# basic_attiny85.net
KiCad netlist of a schematic drawn in EAGLE
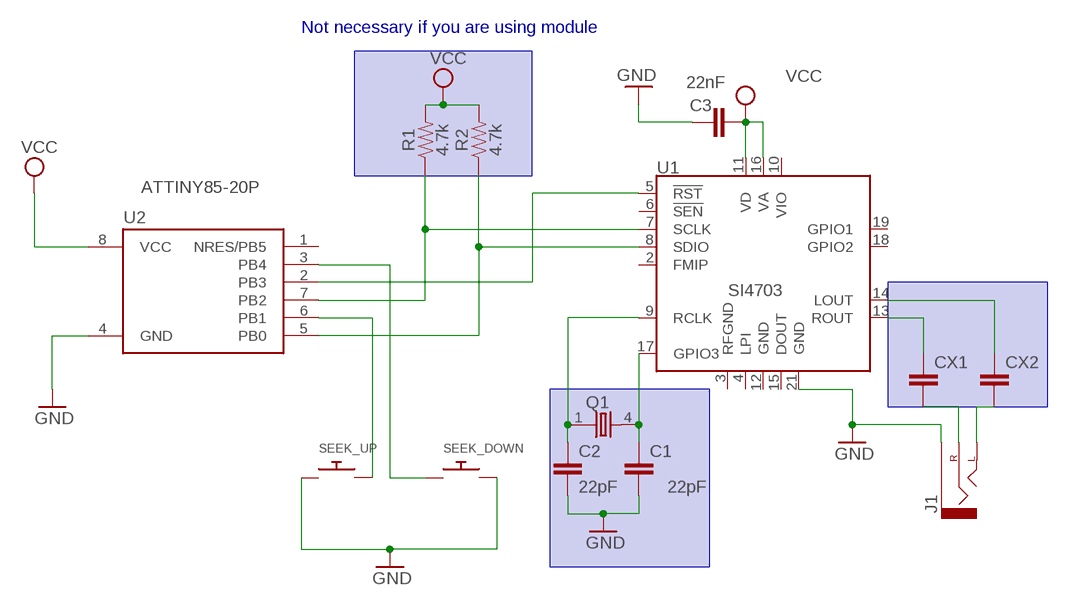
[diagram p0: schematic, sheet 1]

(export (version "E")
  (design (tool "Eeschema 10.0.6"))
  (components
    (comp (ref "C1")
      (value "22pF")
      (footprint "eagle-import:C2.5-3")
      (libsource (lib "eagle-import") (part "C2,5-3"))
    )
    (comp (ref "C2")
      (value "22pF")
      (footprint "eagle-import:C2.5-3")
      (libsource (lib "eagle-import") (part "C2,5-3"))
    )
    (comp (ref "C3")
      (value "22nF")
      (footprint "eagle-import:C2.5-3")
      (libsource (lib "eagle-import") (part "C2,5-3"))
    )
    (comp (ref "CX1")
      (value "CXXC10B6")
      (footprint "eagle-import:XC10B6")
      (libsource (lib "eagle-import") (part "CXXC10B6"))
    )
    (comp (ref "CX2")
      (value "CXXC10B6")
      (footprint "eagle-import:XC10B6")
      (libsource (lib "eagle-import") (part "CXXC10B6"))
    )
    (comp (ref "J1")
      (value "AUDIO_JACK_2.5MM_HOLESONLY")
      (footprint "eagle-import:STEREOJACK2.5MM_SPECIAL_HOLES-ONLY")
      (libsource (lib "eagle-import") (part "AUDIO_JACK_2.5MM_HOLESONLY"))
    )
    (comp (ref "Q1")
      (value "86SMX")
      (footprint "eagle-import:86SMX")
      (fields (field (name "MF") "C-MAC  FREQUENCY PRODUCTS LTD") (field (name "MPN") "XTAL003321- 86SMX"))
      (libsource (lib "eagle-import") (part "86SMX"))
    )
    (comp (ref "R1")
      (value "4.7k")
      (footprint "eagle-import:0603")
      (libsource (lib "eagle-import") (part "4.7KOHM-0603-1/10W-1%"))
    )
    (comp (ref "R2")
      (value "4.7k")
      (footprint "eagle-import:0603")
      (libsource (lib "eagle-import") (part "4.7KOHM-0603-1/10W-1%"))
    )
    (comp (ref "SEEK_DOWN")
      (value "SWITCH_PUSHBUTTONC&K_KSS")
      (footprint "eagle-import:BTN_CK_KSS")
      (libsource (lib "eagle-import") (part "SWITCH_PUSHBUTTONC&K_KSS"))
    )
    (comp (ref "SEEK_UP")
      (value "SWITCH_PUSHBUTTONC&K_KSS")
      (footprint "eagle-import:BTN_CK_KSS")
      (libsource (lib "eagle-import") (part "SWITCH_PUSHBUTTONC&K_KSS"))
    )
    (comp (ref "U1")
      (value "SI4703")
      (footprint "eagle-import:QFN-20-3X3MM")
      (fields (field (name "MF") "SparkFun Electronics"))
      (libsource (lib "eagle-import") (part "SI4703"))
    )
    (comp (ref "U2")
      (value "ATTINY85-20P")
      (footprint "eagle-import:PDIP08_300MIL")
      (libsource (lib "eagle-import") (part "ATTINY85P-20"))
    )
  )
  (nets
    (net (code "1") (name "GND") (class "Default")
      (node (ref "C1") (pin "2") (pinfunction "2_2") (pintype "passive"))
      (node (ref "C2") (pin "2") (pinfunction "2_2") (pintype "passive"))
      (node (ref "C3") (pin "1") (pinfunction "1_1") (pintype "passive"))
      (node (ref "J1") (pin "RING1") (pinfunction "SLEEVE_RING1") (pintype "bidirectional"))
      (node (ref "SEEK_DOWN") (pin "P$2") (pinfunction "P$2_P$2") (pintype "passive"))
      (node (ref "SEEK_UP") (pin "P$1") (pinfunction "P$1_P$1") (pintype "passive"))
      (node (ref "U1") (pin "21") (pinfunction "GND_21") (pintype "bidirectional"))
      (node (ref "U2") (pin "4") (pinfunction "GND_4") (pintype "power_in"))
    )
    (net (code "2") (name "Net-(J1-LEFT)") (class "Default")
      (node (ref "CX2") (pin "2") (pinfunction "2_2") (pintype "passive"))
      (node (ref "J1") (pin "SHIELD") (pinfunction "LEFT_SHIELD") (pintype "bidirectional"))
    )
    (net (code "3") (name "Net-(J1-RIGHT)") (class "Default")
      (node (ref "CX1") (pin "2") (pinfunction "2_2") (pintype "passive"))
      (node (ref "J1") (pin "TIP") (pinfunction "RIGHT_TIP") (pintype "bidirectional"))
    )
    (net (code "4") (name "Net-(Q1-2)") (class "Default")
      (node (ref "C1") (pin "1") (pinfunction "1_1") (pintype "passive"))
      (node (ref "Q1") (pin "4") (pinfunction "2_4") (pintype "passive"))
      (node (ref "U1") (pin "17") (pinfunction "GPIO3_17") (pintype "bidirectional"))
    )
    (net (code "5") (name "Net-(U1-LOUT)") (class "Default")
      (node (ref "CX2") (pin "1") (pinfunction "1_1") (pintype "passive"))
      (node (ref "U1") (pin "14") (pinfunction "LOUT_14") (pintype "bidirectional"))
    )
    (net (code "6") (name "Net-(U1-RCLK)") (class "Default")
      (node (ref "C2") (pin "1") (pinfunction "1_1") (pintype "passive"))
      (node (ref "Q1") (pin "1") (pinfunction "1_1") (pintype "passive"))
      (node (ref "U1") (pin "9") (pinfunction "RCLK_9") (pintype "bidirectional"))
    )
    (net (code "7") (name "Net-(U1-ROUT)") (class "Default")
      (node (ref "CX1") (pin "1") (pinfunction "1_1") (pintype "passive"))
      (node (ref "U1") (pin "13") (pinfunction "ROUT_13") (pintype "bidirectional"))
    )
    (net (code "8") (name "Net-(U1-SCLK)") (class "Default")
      (node (ref "R1") (pin "1") (pinfunction "1_1") (pintype "passive"))
      (node (ref "U1") (pin "7") (pinfunction "SCLK_7") (pintype "bidirectional"))
      (node (ref "U2") (pin "7") (pinfunction "PB2_7") (pintype "bidirectional"))
    )
    (net (code "9") (name "Net-(U1-SDIO)") (class "Default")
      (node (ref "R2") (pin "1") (pinfunction "1_1") (pintype "passive"))
      (node (ref "U1") (pin "8") (pinfunction "SDIO_8") (pintype "bidirectional"))
      (node (ref "U2") (pin "5") (pinfunction "PB0_5") (pintype "bidirectional"))
    )
    (net (code "10") (name "Net-(U1-~{RST})") (class "Default")
      (node (ref "U1") (pin "5") (pinfunction "~{RST}_5") (pintype "bidirectional"))
      (node (ref "U2") (pin "2") (pinfunction "PB3_2") (pintype "bidirectional"))
    )
    (net (code "11") (name "Net-(U2-PB1)") (class "Default")
      (node (ref "SEEK_UP") (pin "P$2") (pinfunction "P$2_P$2") (pintype "passive"))
      (node (ref "U2") (pin "6") (pinfunction "PB1_6") (pintype "bidirectional"))
    )
    (net (code "12") (name "Net-(U2-PB4)") (class "Default")
      (node (ref "SEEK_DOWN") (pin "P$1") (pinfunction "P$1_P$1") (pintype "passive"))
      (node (ref "U2") (pin "3") (pinfunction "PB4_3") (pintype "bidirectional"))
    )
    (net (code "13") (name "VCC") (class "Default")
      (node (ref "C3") (pin "2") (pinfunction "2_2") (pintype "passive"))
      (node (ref "R1") (pin "2") (pinfunction "2_2") (pintype "passive"))
      (node (ref "R2") (pin "2") (pinfunction "2_2") (pintype "passive"))
      (node (ref "U1") (pin "11") (pinfunction "VD_11") (pintype "bidirectional"))
      (node (ref "U1") (pin "16") (pinfunction "VA_16") (pintype "bidirectional"))
      (node (ref "U2") (pin "8") (pinfunction "VCC_8") (pintype "power_in"))
    )
    (net (code "14") (name "unconnected-(U1-DOUT-Pad15)") (class "Default")
      (node (ref "U1") (pin "15") (pinfunction "DOUT_15") (pintype "bidirectional"))
    )
    (net (code "15") (name "unconnected-(U1-FMIP-Pad2)") (class "Default")
      (node (ref "U1") (pin "2") (pinfunction "FMIP_2") (pintype "bidirectional"))
    )
    (net (code "16") (name "unconnected-(U1-GND-Pad12)") (class "Default")
      (node (ref "U1") (pin "12") (pinfunction "GND_12") (pintype "bidirectional"))
    )
    (net (code "17") (name "unconnected-(U1-GPIO1-Pad19)") (class "Default")
      (node (ref "U1") (pin "19") (pinfunction "GPIO1_19") (pintype "bidirectional"))
    )
    (net (code "18") (name "unconnected-(U1-GPIO2-Pad18)") (class "Default")
      (node (ref "U1") (pin "18") (pinfunction "GPIO2_18") (pintype "bidirectional"))
    )
    (net (code "19") (name "unconnected-(U1-LPI-Pad4)") (class "Default")
      (node (ref "U1") (pin "4") (pinfunction "LPI_4") (pintype "bidirectional"))
    )
    (net (code "20") (name "unconnected-(U1-RFGND-Pad3)") (class "Default")
      (node (ref "U1") (pin "3") (pinfunction "RFGND_3") (pintype "bidirectional"))
    )
    (net (code "21") (name "unconnected-(U1-VIO-Pad10)") (class "Default")
      (node (ref "U1") (pin "10") (pinfunction "VIO_10") (pintype "bidirectional"))
    )
    (net (code "22") (name "unconnected-(U1-~{SEN}-Pad6)") (class "Default")
      (node (ref "U1") (pin "6") (pinfunction "~{SEN}_6") (pintype "bidirectional"))
    )
    (net (code "23") (name "unconnected-(U2-NRES{slash}PB5-Pad1)") (class "Default")
      (node (ref "U2") (pin "1") (pinfunction "NRES/PB5_1") (pintype "bidirectional"))
    )
  )
)
